# Knob.net
KiCad netlist of a schematic drawn in EAGLE
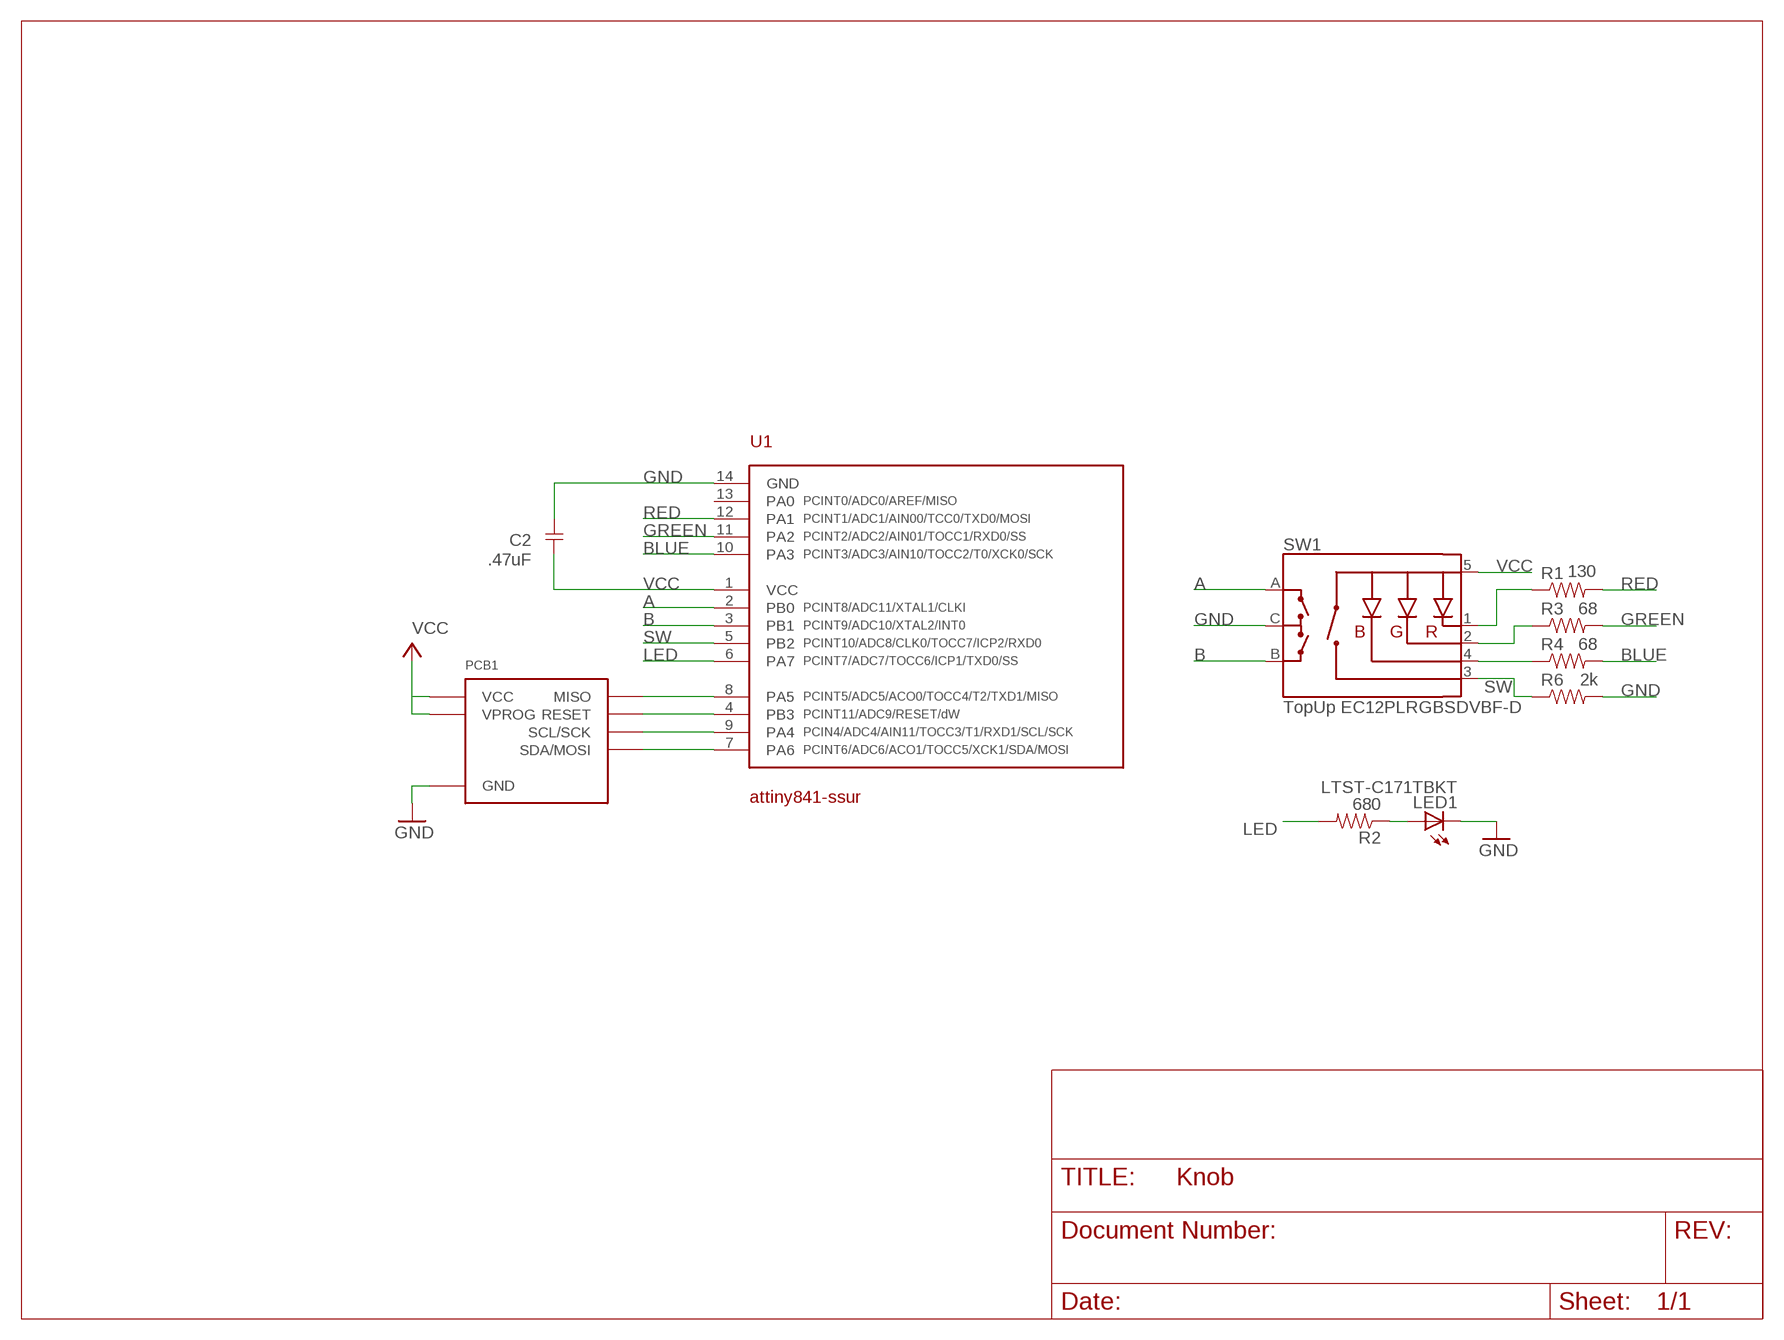
[diagram p0: schematic, sheet 1]

(export (version "E")
  (design (tool "Eeschema 10.0.6"))
  (components
    (comp (ref "C2")
      (value ".47uF")
      (footprint "eagle-import:0805")
      (libsource (lib "eagle-import") (part "CAPACITOR"))
    )
    (comp (ref "LED1")
      (value "LTST-C171TBKT")
      (footprint "eagle-import:0805-LED")
      (libsource (lib "eagle-import") (part "LED-0805-BLUE"))
    )
    (comp (ref "PCB1")
      (value "MAGDEVICE")
      (footprint "eagle-import:MAGDEVICE")
      (libsource (lib "eagle-import") (part "MAGDEVICE"))
    )
    (comp (ref "R1")
      (value "130")
      (footprint "eagle-import:0805")
      (libsource (lib "eagle-import") (part "RESISTOR"))
    )
    (comp (ref "R2")
      (value "680")
      (footprint "eagle-import:0805")
      (libsource (lib "eagle-import") (part "RESISTOR"))
    )
    (comp (ref "R3")
      (value "68")
      (footprint "eagle-import:0805")
      (libsource (lib "eagle-import") (part "RESISTOR"))
    )
    (comp (ref "R4")
      (value "68")
      (footprint "eagle-import:0805")
      (libsource (lib "eagle-import") (part "RESISTOR"))
    )
    (comp (ref "R6")
      (value "2k")
      (footprint "eagle-import:0805")
      (libsource (lib "eagle-import") (part "RESISTOR"))
    )
    (comp (ref "SW1")
      (value "TopUp EC12PLRGBSDVBF-D")
      (footprint "eagle-import:ENCODER_LED_3")
      (libsource (lib "eagle-import") (part "ENCODER_RGB_CA"))
    )
    (comp (ref "U1")
      (value "attiny841-ssur")
      (footprint "eagle-import:SOIC14")
      (libsource (lib "eagle-import") (part "ATTINY841"))
    )
  )
  (nets
    (net (code "1") (name "/A") (class "Default")
      (node (ref "SW1") (pin "A") (pinfunction "A_A") (pintype "bidirectional"))
      (node (ref "U1") (pin "2") (pinfunction "PB0_2") (pintype "bidirectional"))
    )
    (net (code "2") (name "/B") (class "Default")
      (node (ref "SW1") (pin "B") (pinfunction "B_B") (pintype "bidirectional"))
      (node (ref "U1") (pin "3") (pinfunction "PB1_3") (pintype "bidirectional"))
    )
    (net (code "3") (name "/BLUE") (class "Default")
      (node (ref "R4") (pin "2") (pinfunction "2_2") (pintype "passive"))
      (node (ref "U1") (pin "10") (pinfunction "PA3_10") (pintype "bidirectional"))
    )
    (net (code "4") (name "/GREEN") (class "Default")
      (node (ref "R3") (pin "2") (pinfunction "2_2") (pintype "passive"))
      (node (ref "U1") (pin "11") (pinfunction "PA2_11") (pintype "bidirectional"))
    )
    (net (code "5") (name "/LED") (class "Default")
      (node (ref "R2") (pin "2") (pinfunction "2_2") (pintype "passive"))
      (node (ref "U1") (pin "6") (pinfunction "PA7_6") (pintype "bidirectional"))
    )
    (net (code "6") (name "/RED") (class "Default")
      (node (ref "R1") (pin "2") (pinfunction "2_2") (pintype "passive"))
      (node (ref "U1") (pin "12") (pinfunction "PA1_12") (pintype "bidirectional"))
    )
    (net (code "7") (name "/SW") (class "Default")
      (node (ref "R6") (pin "1") (pinfunction "1_1") (pintype "passive"))
      (node (ref "SW1") (pin "3") (pinfunction "SW_3") (pintype "passive"))
      (node (ref "U1") (pin "5") (pinfunction "PB2_5") (pintype "bidirectional"))
    )
    (net (code "8") (name "GND") (class "Default")
      (node (ref "C2") (pin "2") (pinfunction "2_2") (pintype "passive"))
      (node (ref "LED1") (pin "C") (pinfunction "C_C") (pintype "passive"))
      (node (ref "PCB1") (pin "GNDA") (pinfunction "GND_GNDA") (pintype "bidirectional"))
      (node (ref "PCB1") (pin "GNDB") (pinfunction "GND_GNDB") (pintype "bidirectional"))
      (node (ref "R6") (pin "2") (pinfunction "2_2") (pintype "passive"))
      (node (ref "SW1") (pin "C") (pinfunction "C_C") (pintype "bidirectional"))
      (node (ref "U1") (pin "14") (pinfunction "GND_14") (pintype "bidirectional"))
    )
    (net (code "9") (name "Net-(LED1-PadA)") (class "Default")
      (node (ref "LED1") (pin "A") (pinfunction "A_A") (pintype "passive"))
      (node (ref "R2") (pin "1") (pinfunction "1_1") (pintype "passive"))
    )
    (net (code "10") (name "Net-(SW1--B)") (class "Default")
      (node (ref "R4") (pin "1") (pinfunction "1_1") (pintype "passive"))
      (node (ref "SW1") (pin "4") (pinfunction "-B_4") (pintype "passive"))
    )
    (net (code "11") (name "Net-(SW1--G)") (class "Default")
      (node (ref "R3") (pin "1") (pinfunction "1_1") (pintype "passive"))
      (node (ref "SW1") (pin "2") (pinfunction "-G_2") (pintype "passive"))
    )
    (net (code "12") (name "Net-(SW1--R)") (class "Default")
      (node (ref "R1") (pin "1") (pinfunction "1_1") (pintype "passive"))
      (node (ref "SW1") (pin "1") (pinfunction "-R_1") (pintype "passive"))
    )
    (net (code "13") (name "Net-(U1-PA4)") (class "Default")
      (node (ref "PCB1") (pin "SCLA") (pinfunction "SCL/SCK_SCLA") (pintype "bidirectional"))
      (node (ref "PCB1") (pin "SCLB") (pinfunction "SCL/SCK_SCLB") (pintype "bidirectional"))
      (node (ref "U1") (pin "9") (pinfunction "PA4_9") (pintype "bidirectional"))
    )
    (net (code "14") (name "Net-(U1-PA5)") (class "Default")
      (node (ref "PCB1") (pin "MISO") (pinfunction "MISO_MISO") (pintype "bidirectional"))
      (node (ref "U1") (pin "8") (pinfunction "PA5_8") (pintype "bidirectional"))
    )
    (net (code "15") (name "Net-(U1-PA6)") (class "Default")
      (node (ref "PCB1") (pin "SDAA") (pinfunction "SDA/MOSI_SDAA") (pintype "bidirectional"))
      (node (ref "PCB1") (pin "SDAB") (pinfunction "SDA/MOSI_SDAB") (pintype "bidirectional"))
      (node (ref "U1") (pin "7") (pinfunction "PA6_7") (pintype "bidirectional"))
    )
    (net (code "16") (name "Net-(U1-PB3)") (class "Default")
      (node (ref "PCB1") (pin "RESET") (pinfunction "RESET_RESET") (pintype "bidirectional"))
      (node (ref "U1") (pin "4") (pinfunction "PB3_4") (pintype "bidirectional"))
    )
    (net (code "17") (name "VCC") (class "Default")
      (node (ref "C2") (pin "1") (pinfunction "1_1") (pintype "passive"))
      (node (ref "PCB1") (pin "VCCA") (pinfunction "VCC_VCCA") (pintype "bidirectional"))
      (node (ref "PCB1") (pin "VCCB") (pinfunction "VCC_VCCB") (pintype "bidirectional"))
      (node (ref "PCB1") (pin "VPROG") (pinfunction "VPROG_VPROG") (pintype "bidirectional"))
      (node (ref "SW1") (pin "5") (pinfunction "+_5") (pintype "passive"))
      (node (ref "U1") (pin "1") (pinfunction "VCC_1") (pintype "bidirectional"))
    )
    (net (code "18") (name "unconnected-(U1-PA0-Pad13)") (class "Default")
      (node (ref "U1") (pin "13") (pinfunction "PA0_13") (pintype "bidirectional"))
    )
  )
)
